# FPGA.net
KiCad netlist of a schematic drawn in Altium Designer
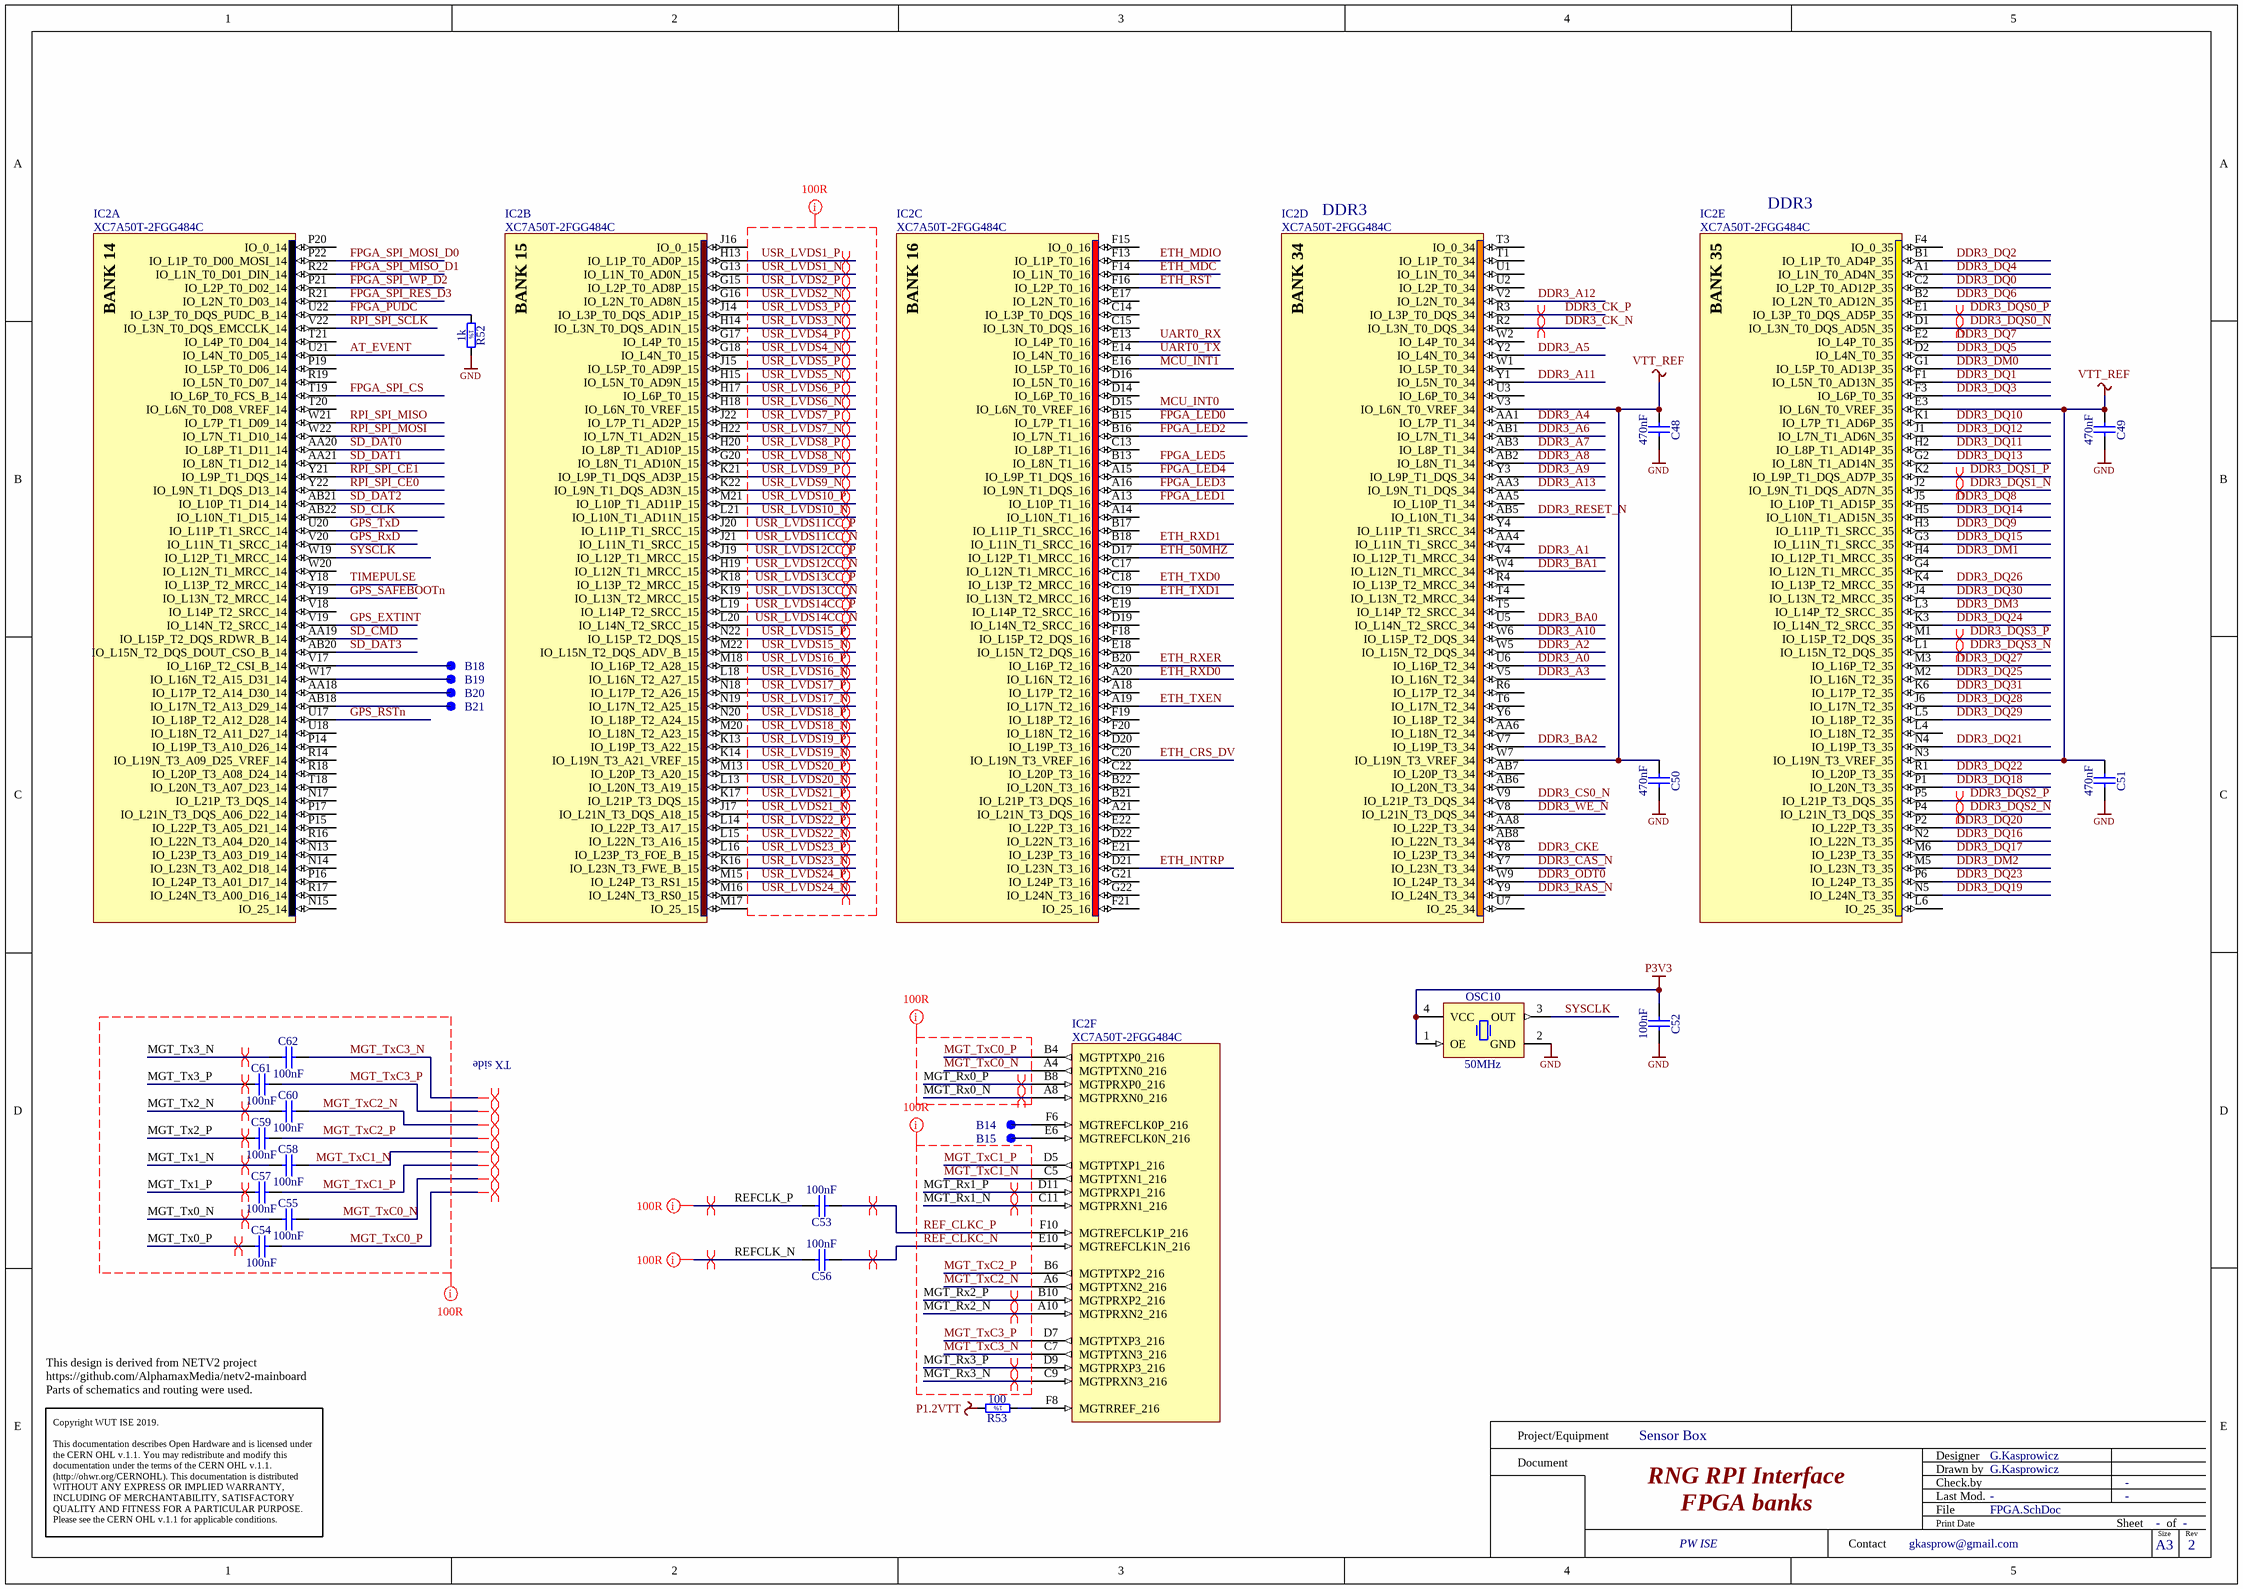
[diagram p0: FPGA.SchDoc]

(export (version "E")
  (design (tool "Eeschema 10.0.6"))
  (components
    (comp (ref "B14")
      (value "SMD Pad")
      (footprint "C100")
      (description "Through Hole Pad")
      (fields (field (name "PART NUMBER") "SMD_PAD_D1MM") (field (name "AUTHOR") "CERN DEM JLC"))
      (libsource (lib "Eletro-mechanical") (part "Single SMD Pad (Round)"))
    )
    (comp (ref "B15")
      (value "SMD Pad")
      (footprint "C100")
      (description "Through Hole Pad")
      (fields (field (name "PART NUMBER") "SMD_PAD_D1MM") (field (name "AUTHOR") "CERN DEM JLC"))
      (libsource (lib "Eletro-mechanical") (part "Single SMD Pad (Round)"))
    )
    (comp (ref "B18")
      (value "SMD Pad")
      (footprint "C100")
      (description "Through Hole Pad")
      (fields (field (name "PART NUMBER") "SMD_PAD_D1MM") (field (name "AUTHOR") "CERN DEM JLC"))
      (libsource (lib "Eletro-mechanical") (part "Single SMD Pad (Round)"))
    )
    (comp (ref "B19")
      (value "SMD Pad")
      (footprint "C100")
      (description "Through Hole Pad")
      (fields (field (name "PART NUMBER") "SMD_PAD_D1MM") (field (name "AUTHOR") "CERN DEM JLC"))
      (libsource (lib "Eletro-mechanical") (part "Single SMD Pad (Round)"))
    )
    (comp (ref "B20")
      (value "SMD Pad")
      (footprint "C100")
      (description "Through Hole Pad")
      (fields (field (name "PART NUMBER") "SMD_PAD_D1MM") (field (name "AUTHOR") "CERN DEM JLC"))
      (libsource (lib "Eletro-mechanical") (part "Single SMD Pad (Round)"))
    )
    (comp (ref "B21")
      (value "SMD Pad")
      (footprint "C100")
      (description "Through Hole Pad")
      (fields (field (name "PART NUMBER") "SMD_PAD_D1MM") (field (name "AUTHOR") "CERN DEM JLC"))
      (libsource (lib "Eletro-mechanical") (part "Single SMD Pad (Round)"))
    )
    (comp (ref "C48")
      (value "470nF")
      (footprint "CAPC0603X33N")
      (description "Non-polarised capacitor")
      (fields
        (field (name "PART NUMBER") "CC0201_470NF_4V_20%_X5R")
        (field (name "VOLTAGE") "4V")
        (field (name "AUTHOR") "CERN DEM JLC")
      )
      (libsource (lib "Capacitors") (part "Capacitor - non polarized"))
    )
    (comp (ref "C49")
      (value "470nF")
      (footprint "CAPC0603X33N")
      (description "Non-polarised capacitor")
      (fields
        (field (name "PART NUMBER") "CC0201_470NF_4V_20%_X5R")
        (field (name "VOLTAGE") "4V")
        (field (name "AUTHOR") "CERN DEM JLC")
      )
      (libsource (lib "Capacitors") (part "Capacitor - non polarized"))
    )
    (comp (ref "C50")
      (value "470nF")
      (footprint "CAPC0603X33N")
      (description "Non-polarised capacitor")
      (fields
        (field (name "PART NUMBER") "CC0201_470NF_4V_20%_X5R")
        (field (name "VOLTAGE") "4V")
        (field (name "AUTHOR") "CERN DEM JLC")
      )
      (libsource (lib "Capacitors") (part "Capacitor - non polarized"))
    )
    (comp (ref "C51")
      (value "470nF")
      (footprint "CAPC0603X33N")
      (description "Non-polarised capacitor")
      (fields
        (field (name "PART NUMBER") "CC0201_470NF_4V_20%_X5R")
        (field (name "VOLTAGE") "4V")
        (field (name "AUTHOR") "CERN DEM JLC")
      )
      (libsource (lib "Capacitors") (part "Capacitor - non polarized"))
    )
    (comp (ref "C52")
      (value "100nF")
      (footprint "CAPC0603X33N")
      (description "Non-polarised capacitor")
      (fields
        (field (name "PART NUMBER") "CC0201_100NF_6.3V_10%_X5R")
        (field (name "VOLTAGE") "6.3V")
        (field (name "AUTHOR") "CERN DEM JLC")
      )
      (libsource (lib "Capacitors") (part "Capacitor - non polarized"))
    )
    (comp (ref "C53")
      (value "100nF")
      (footprint "CAPC0603X33N")
      (description "Non-polarised capacitor")
      (fields
        (field (name "PART NUMBER") "CC0201_100NF_6.3V_10%_X5R")
        (field (name "VOLTAGE") "6.3V")
        (field (name "AUTHOR") "CERN DEM JLC")
      )
      (libsource (lib "Capacitors") (part "Capacitor - non polarized"))
    )
    (comp (ref "C54")
      (value "100nF")
      (footprint "CAPC0603X33N")
      (description "Non-polarised capacitor")
      (fields
        (field (name "PART NUMBER") "CC0201_100NF_6.3V_10%_X5R")
        (field (name "VOLTAGE") "6.3V")
        (field (name "AUTHOR") "CERN DEM JLC")
      )
      (libsource (lib "Capacitors") (part "Capacitor - non polarized"))
    )
    (comp (ref "C55")
      (value "100nF")
      (footprint "CAPC0603X33N")
      (description "Non-polarised capacitor")
      (fields
        (field (name "PART NUMBER") "CC0201_100NF_6.3V_10%_X5R")
        (field (name "VOLTAGE") "6.3V")
        (field (name "AUTHOR") "CERN DEM JLC")
      )
      (libsource (lib "Capacitors") (part "Capacitor - non polarized"))
    )
    (comp (ref "C56")
      (value "100nF")
      (footprint "CAPC0603X33N")
      (description "Non-polarised capacitor")
      (fields
        (field (name "PART NUMBER") "CC0201_100NF_6.3V_10%_X5R")
        (field (name "VOLTAGE") "6.3V")
        (field (name "AUTHOR") "CERN DEM JLC")
      )
      (libsource (lib "Capacitors") (part "Capacitor - non polarized"))
    )
    (comp (ref "C57")
      (value "100nF")
      (footprint "CAPC0603X33N")
      (description "Non-polarised capacitor")
      (fields
        (field (name "PART NUMBER") "CC0201_100NF_6.3V_10%_X5R")
        (field (name "VOLTAGE") "6.3V")
        (field (name "AUTHOR") "CERN DEM JLC")
      )
      (libsource (lib "Capacitors") (part "Capacitor - non polarized"))
    )
    (comp (ref "C58")
      (value "100nF")
      (footprint "CAPC0603X33N")
      (description "Non-polarised capacitor")
      (fields
        (field (name "PART NUMBER") "CC0201_100NF_6.3V_10%_X5R")
        (field (name "VOLTAGE") "6.3V")
        (field (name "AUTHOR") "CERN DEM JLC")
      )
      (libsource (lib "Capacitors") (part "Capacitor - non polarized"))
    )
    (comp (ref "C59")
      (value "100nF")
      (footprint "CAPC0603X33N")
      (description "Non-polarised capacitor")
      (fields
        (field (name "PART NUMBER") "CC0201_100NF_6.3V_10%_X5R")
        (field (name "VOLTAGE") "6.3V")
        (field (name "AUTHOR") "CERN DEM JLC")
      )
      (libsource (lib "Capacitors") (part "Capacitor - non polarized"))
    )
    (comp (ref "C60")
      (value "100nF")
      (footprint "CAPC0603X33N")
      (description "Non-polarised capacitor")
      (fields
        (field (name "PART NUMBER") "CC0201_100NF_6.3V_10%_X5R")
        (field (name "VOLTAGE") "6.3V")
        (field (name "AUTHOR") "CERN DEM JLC")
      )
      (libsource (lib "Capacitors") (part "Capacitor - non polarized"))
    )
    (comp (ref "C61")
      (value "100nF")
      (footprint "CAPC0603X33N")
      (description "Non-polarised capacitor")
      (fields
        (field (name "PART NUMBER") "CC0201_100NF_6.3V_10%_X5R")
        (field (name "VOLTAGE") "6.3V")
        (field (name "AUTHOR") "CERN DEM JLC")
      )
      (libsource (lib "Capacitors") (part "Capacitor - non polarized"))
    )
    (comp (ref "C62")
      (value "100nF")
      (footprint "CAPC0603X33N")
      (description "Non-polarised capacitor")
      (fields
        (field (name "PART NUMBER") "CC0201_100NF_6.3V_10%_X5R")
        (field (name "VOLTAGE") "6.3V")
        (field (name "AUTHOR") "CERN DEM JLC")
      )
      (libsource (lib "Capacitors") (part "Capacitor - non polarized"))
    )
    (comp (ref "IC2")
      (value "XC7A50T-2FGG484C")
      (footprint "BGA484C100P22X22_2300X2300X260")
      (fields (field (name "MANUFACTURER") "XILINX") (field (name "AUTHOR") "CERN DEM JMW"))
      (libsource (lib "ICs And Semiconductors") (part "XC7A50T-2FGG484C"))
    )
    (comp (ref "OSC10")
      (value "50MHz")
      (footprint "OSCSC254P320X500X130-4N")
      (description "Oscillator 4 pins 1=OE 2=GND 3=OUT 4=VCC")
      (fields
        (field (name "PART NUMBER") "OSC_50MHZ_CTS_636L3I050M00000")
        (field (name "MANUFACTURER") "CTS ELECTRONIC COMPONENTS")
        (field (name "AUTHOR") "CERN DEM JMW")
      )
      (libsource (lib "ICs And Semiconductors") (part "Oscillator 1OE 2GND 3OUT 4VCC"))
    )
    (comp (ref "R52")
      (value "1k")
      (footprint "RESC1005X40N")
      (description "Resistor - 1%")
      (fields
        (field (name "PART NUMBER") "R0402_1K_1%_0.0625W_100PPM")
        (field (name "POWER") "0.0625W")
        (field (name "AUTHOR") "CERN DEM JLC")
      )
      (libsource (lib "Resistors") (part "Resistor - 1%"))
    )
    (comp (ref "R53")
      (value "100")
      (footprint "RESC1005X40N")
      (description "Resistor - 1%")
      (fields
        (field (name "PART NUMBER") "R0402_100R_1%_0.1W_100PPM")
        (field (name "POWER") "0.1W")
        (field (name "AUTHOR") "CERN DEM JLC")
      )
      (libsource (lib "Resistors") (part "Resistor - 1%"))
    )
  )
  (nets
    (net (code "1") (name "/AT_EVENT") (class "Default")
      (node (ref "IC2") (pin "U21") (pinfunction "IO_L4N_T0_D05_14_U21") (pintype "bidirectional"))
    )
    (net (code "2") (name "/DDR3_A0") (class "Default")
      (node (ref "IC2") (pin "U6") (pinfunction "IO_L16P_T2_34_U6") (pintype "bidirectional"))
    )
    (net (code "3") (name "/DDR3_A1") (class "Default")
      (node (ref "IC2") (pin "V4") (pinfunction "IO_L12P_T1_MRCC_34_V4") (pintype "bidirectional"))
    )
    (net (code "4") (name "/DDR3_A2") (class "Default")
      (node (ref "IC2") (pin "W5") (pinfunction "IO_L15N_T2_DQS_34_W5") (pintype "bidirectional"))
    )
    (net (code "5") (name "/DDR3_A3") (class "Default")
      (node (ref "IC2") (pin "V5") (pinfunction "IO_L16N_T2_34_V5") (pintype "bidirectional"))
    )
    (net (code "6") (name "/DDR3_A4") (class "Default")
      (node (ref "IC2") (pin "AA1") (pinfunction "IO_L7P_T1_34_AA1") (pintype "bidirectional"))
    )
    (net (code "7") (name "/DDR3_A5") (class "Default")
      (node (ref "IC2") (pin "Y2") (pinfunction "IO_L4N_T0_34_Y2") (pintype "bidirectional"))
    )
    (net (code "8") (name "/DDR3_A6") (class "Default")
      (node (ref "IC2") (pin "AB1") (pinfunction "IO_L7N_T1_34_AB1") (pintype "bidirectional"))
    )
    (net (code "9") (name "/DDR3_A7") (class "Default")
      (node (ref "IC2") (pin "AB3") (pinfunction "IO_L8P_T1_34_AB3") (pintype "bidirectional"))
    )
    (net (code "10") (name "/DDR3_A8") (class "Default")
      (node (ref "IC2") (pin "AB2") (pinfunction "IO_L8N_T1_34_AB2") (pintype "bidirectional"))
    )
    (net (code "11") (name "/DDR3_A9") (class "Default")
      (node (ref "IC2") (pin "Y3") (pinfunction "IO_L9P_T1_DQS_34_Y3") (pintype "bidirectional"))
    )
    (net (code "12") (name "/DDR3_A10") (class "Default")
      (node (ref "IC2") (pin "W6") (pinfunction "IO_L15P_T2_DQS_34_W6") (pintype "bidirectional"))
    )
    (net (code "13") (name "/DDR3_A11") (class "Default")
      (node (ref "IC2") (pin "Y1") (pinfunction "IO_L5N_T0_34_Y1") (pintype "bidirectional"))
    )
    (net (code "14") (name "/DDR3_A12") (class "Default")
      (node (ref "IC2") (pin "V2") (pinfunction "IO_L2N_T0_34_V2") (pintype "bidirectional"))
    )
    (net (code "15") (name "/DDR3_A13") (class "Default")
      (node (ref "IC2") (pin "AA3") (pinfunction "IO_L9N_T1_DQS_34_AA3") (pintype "bidirectional"))
    )
    (net (code "16") (name "/DDR3_BA0") (class "Default")
      (node (ref "IC2") (pin "U5") (pinfunction "IO_L14N_T2_SRCC_34_U5") (pintype "bidirectional"))
    )
    (net (code "17") (name "/DDR3_BA1") (class "Default")
      (node (ref "IC2") (pin "W4") (pinfunction "IO_L12N_T1_MRCC_34_W4") (pintype "bidirectional"))
    )
    (net (code "18") (name "/DDR3_BA2") (class "Default")
      (node (ref "IC2") (pin "V7") (pinfunction "IO_L19P_T3_34_V7") (pintype "bidirectional"))
    )
    (net (code "19") (name "/DDR3_CAS_N") (class "Default")
      (node (ref "IC2") (pin "Y7") (pinfunction "IO_L23N_T3_34_Y7") (pintype "bidirectional"))
    )
    (net (code "20") (name "/DDR3_CKE") (class "Default")
      (node (ref "IC2") (pin "Y8") (pinfunction "IO_L23P_T3_34_Y8") (pintype "bidirectional"))
    )
    (net (code "21") (name "/DDR3_CK_N") (class "Default")
      (node (ref "IC2") (pin "R2") (pinfunction "IO_L3N_T0_DQS_34_R2") (pintype "bidirectional"))
    )
    (net (code "22") (name "/DDR3_CK_P") (class "Default")
      (node (ref "IC2") (pin "R3") (pinfunction "IO_L3P_T0_DQS_34_R3") (pintype "bidirectional"))
    )
    (net (code "23") (name "/DDR3_CS0_N") (class "Default")
      (node (ref "IC2") (pin "V9") (pinfunction "IO_L21P_T3_DQS_34_V9") (pintype "bidirectional"))
    )
    (net (code "24") (name "/DDR3_DM0") (class "Default")
      (node (ref "IC2") (pin "G1") (pinfunction "IO_L5P_T0_AD13P_35_G1") (pintype "bidirectional"))
    )
    (net (code "25") (name "/DDR3_DM1") (class "Default")
      (node (ref "IC2") (pin "H4") (pinfunction "IO_L12P_T1_MRCC_35_H4") (pintype "bidirectional"))
    )
    (net (code "26") (name "/DDR3_DM2") (class "Default")
      (node (ref "IC2") (pin "M5") (pinfunction "IO_L23N_T3_35_M5") (pintype "bidirectional"))
    )
    (net (code "27") (name "/DDR3_DM3") (class "Default")
      (node (ref "IC2") (pin "L3") (pinfunction "IO_L14P_T2_SRCC_35_L3") (pintype "bidirectional"))
    )
    (net (code "28") (name "/DDR3_DQ0") (class "Default")
      (node (ref "IC2") (pin "C2") (pinfunction "IO_L2P_T0_AD12P_35_C2") (pintype "bidirectional"))
    )
    (net (code "29") (name "/DDR3_DQ1") (class "Default")
      (node (ref "IC2") (pin "F1") (pinfunction "IO_L5N_T0_AD13N_35_F1") (pintype "bidirectional"))
    )
    (net (code "30") (name "/DDR3_DQ2") (class "Default")
      (node (ref "IC2") (pin "B1") (pinfunction "IO_L1P_T0_AD4P_35_B1") (pintype "bidirectional"))
    )
    (net (code "31") (name "/DDR3_DQ3") (class "Default")
      (node (ref "IC2") (pin "F3") (pinfunction "IO_L6P_T0_35_F3") (pintype "bidirectional"))
    )
    (net (code "32") (name "/DDR3_DQ4") (class "Default")
      (node (ref "IC2") (pin "A1") (pinfunction "IO_L1N_T0_AD4N_35_A1") (pintype "bidirectional"))
    )
    (net (code "33") (name "/DDR3_DQ5") (class "Default")
      (node (ref "IC2") (pin "D2") (pinfunction "IO_L4N_T0_35_D2") (pintype "bidirectional"))
    )
    (net (code "34") (name "/DDR3_DQ6") (class "Default")
      (node (ref "IC2") (pin "B2") (pinfunction "IO_L2N_T0_AD12N_35_B2") (pintype "bidirectional"))
    )
    (net (code "35") (name "/DDR3_DQ7") (class "Default")
      (node (ref "IC2") (pin "E2") (pinfunction "IO_L4P_T0_35_E2") (pintype "bidirectional"))
    )
    (net (code "36") (name "/DDR3_DQ8") (class "Default")
      (node (ref "IC2") (pin "J5") (pinfunction "IO_L10P_T1_AD15P_35_J5") (pintype "bidirectional"))
    )
    (net (code "37") (name "/DDR3_DQ9") (class "Default")
      (node (ref "IC2") (pin "H3") (pinfunction "IO_L11P_T1_SRCC_35_H3") (pintype "bidirectional"))
    )
    (net (code "38") (name "/DDR3_DQ10") (class "Default")
      (node (ref "IC2") (pin "K1") (pinfunction "IO_L7P_T1_AD6P_35_K1") (pintype "bidirectional"))
    )
    (net (code "39") (name "/DDR3_DQ11") (class "Default")
      (node (ref "IC2") (pin "H2") (pinfunction "IO_L8P_T1_AD14P_35_H2") (pintype "bidirectional"))
    )
    (net (code "40") (name "/DDR3_DQ12") (class "Default")
      (node (ref "IC2") (pin "J1") (pinfunction "IO_L7N_T1_AD6N_35_J1") (pintype "bidirectional"))
    )
    (net (code "41") (name "/DDR3_DQ13") (class "Default")
      (node (ref "IC2") (pin "G2") (pinfunction "IO_L8N_T1_AD14N_35_G2") (pintype "bidirectional"))
    )
    (net (code "42") (name "/DDR3_DQ14") (class "Default")
      (node (ref "IC2") (pin "H5") (pinfunction "IO_L10N_T1_AD15N_35_H5") (pintype "bidirectional"))
    )
    (net (code "43") (name "/DDR3_DQ15") (class "Default")
      (node (ref "IC2") (pin "G3") (pinfunction "IO_L11N_T1_SRCC_35_G3") (pintype "bidirectional"))
    )
    (net (code "44") (name "/DDR3_DQ16") (class "Default")
      (node (ref "IC2") (pin "N2") (pinfunction "IO_L22N_T3_35_N2") (pintype "bidirectional"))
    )
    (net (code "45") (name "/DDR3_DQ17") (class "Default")
      (node (ref "IC2") (pin "M6") (pinfunction "IO_L23P_T3_35_M6") (pintype "bidirectional"))
    )
    (net (code "46") (name "/DDR3_DQ18") (class "Default")
      (node (ref "IC2") (pin "P1") (pinfunction "IO_L20N_T3_35_P1") (pintype "bidirectional"))
    )
    (net (code "47") (name "/DDR3_DQ19") (class "Default")
      (node (ref "IC2") (pin "N5") (pinfunction "IO_L24N_T3_35_N5") (pintype "bidirectional"))
    )
    (net (code "48") (name "/DDR3_DQ20") (class "Default")
      (node (ref "IC2") (pin "P2") (pinfunction "IO_L22P_T3_35_P2") (pintype "bidirectional"))
    )
    (net (code "49") (name "/DDR3_DQ21") (class "Default")
      (node (ref "IC2") (pin "N4") (pinfunction "IO_L19P_T3_35_N4") (pintype "bidirectional"))
    )
    (net (code "50") (name "/DDR3_DQ22") (class "Default")
      (node (ref "IC2") (pin "R1") (pinfunction "IO_L20P_T3_35_R1") (pintype "bidirectional"))
    )
    (net (code "51") (name "/DDR3_DQ23") (class "Default")
      (node (ref "IC2") (pin "P6") (pinfunction "IO_L24P_T3_35_P6") (pintype "bidirectional"))
    )
    (net (code "52") (name "/DDR3_DQ24") (class "Default")
      (node (ref "IC2") (pin "K3") (pinfunction "IO_L14N_T2_SRCC_35_K3") (pintype "bidirectional"))
    )
    (net (code "53") (name "/DDR3_DQ25") (class "Default")
      (node (ref "IC2") (pin "M2") (pinfunction "IO_L16N_T2_35_M2") (pintype "bidirectional"))
    )
    (net (code "54") (name "/DDR3_DQ26") (class "Default")
      (node (ref "IC2") (pin "K4") (pinfunction "IO_L13P_T2_MRCC_35_K4") (pintype "bidirectional"))
    )
    (net (code "55") (name "/DDR3_DQ27") (class "Default")
      (node (ref "IC2") (pin "M3") (pinfunction "IO_L16P_T2_35_M3") (pintype "bidirectional"))
    )
    (net (code "56") (name "/DDR3_DQ28") (class "Default")
      (node (ref "IC2") (pin "J6") (pinfunction "IO_L17N_T2_35_J6") (pintype "bidirectional"))
    )
    (net (code "57") (name "/DDR3_DQ29") (class "Default")
      (node (ref "IC2") (pin "L5") (pinfunction "IO_L18P_T2_35_L5") (pintype "bidirectional"))
    )
    (net (code "58") (name "/DDR3_DQ30") (class "Default")
      (node (ref "IC2") (pin "J4") (pinfunction "IO_L13N_T2_MRCC_35_J4") (pintype "bidirectional"))
    )
    (net (code "59") (name "/DDR3_DQ31") (class "Default")
      (node (ref "IC2") (pin "K6") (pinfunction "IO_L17P_T2_35_K6") (pintype "bidirectional"))
    )
    (net (code "60") (name "/DDR3_DQS0_N") (class "Default")
      (node (ref "IC2") (pin "D1") (pinfunction "IO_L3N_T0_DQS_AD5N_35_D1") (pintype "bidirectional"))
    )
    (net (code "61") (name "/DDR3_DQS0_P") (class "Default")
      (node (ref "IC2") (pin "E1") (pinfunction "IO_L3P_T0_DQS_AD5P_35_E1") (pintype "bidirectional"))
    )
    (net (code "62") (name "/DDR3_DQS1_N") (class "Default")
      (node (ref "IC2") (pin "J2") (pinfunction "IO_L9N_T1_DQS_AD7N_35_J2") (pintype "bidirectional"))
    )
    (net (code "63") (name "/DDR3_DQS1_P") (class "Default")
      (node (ref "IC2") (pin "K2") (pinfunction "IO_L9P_T1_DQS_AD7P_35_K2") (pintype "bidirectional"))
    )
    (net (code "64") (name "/DDR3_DQS2_N") (class "Default")
      (node (ref "IC2") (pin "P4") (pinfunction "IO_L21N_T3_DQS_35_P4") (pintype "bidirectional"))
    )
    (net (code "65") (name "/DDR3_DQS2_P") (class "Default")
      (node (ref "IC2") (pin "P5") (pinfunction "IO_L21P_T3_DQS_35_P5") (pintype "bidirectional"))
    )
    (net (code "66") (name "/DDR3_DQS3_N") (class "Default")
      (node (ref "IC2") (pin "L1") (pinfunction "IO_L15N_T2_DQS_35_L1") (pintype "bidirectional"))
    )
    (net (code "67") (name "/DDR3_DQS3_P") (class "Default")
      (node (ref "IC2") (pin "M1") (pinfunction "IO_L15P_T2_DQS_35_M1") (pintype "bidirectional"))
    )
    (net (code "68") (name "/DDR3_ODT0") (class "Default")
      (node (ref "IC2") (pin "W9") (pinfunction "IO_L24P_T3_34_W9") (pintype "bidirectional"))
    )
    (net (code "69") (name "/DDR3_RAS_N") (class "Default")
      (node (ref "IC2") (pin "Y9") (pinfunction "IO_L24N_T3_34_Y9") (pintype "bidirectional"))
    )
    (net (code "70") (name "/DDR3_RESET_N") (class "Default")
      (node (ref "IC2") (pin "AB5") (pinfunction "IO_L10N_T1_34_AB5") (pintype "bidirectional"))
    )
    (net (code "71") (name "/DDR3_WE_N") (class "Default")
      (node (ref "IC2") (pin "V8") (pinfunction "IO_L21N_T3_DQS_34_V8") (pintype "bidirectional"))
    )
    (net (code "72") (name "/ETH_50MHZ") (class "Default")
      (node (ref "IC2") (pin "D17") (pinfunction "IO_L12P_T1_MRCC_16_D17") (pintype "bidirectional"))
    )
    (net (code "73") (name "/ETH_CRS_DV") (class "Default")
      (node (ref "IC2") (pin "C20") (pinfunction "IO_L19N_T3_VREF_16_C20") (pintype "bidirectional"))
    )
    (net (code "74") (name "/ETH_INTRP") (class "Default")
      (node (ref "IC2") (pin "D21") (pinfunction "IO_L23N_T3_16_D21") (pintype "bidirectional"))
    )
    (net (code "75") (name "/ETH_MDC") (class "Default")
      (node (ref "IC2") (pin "F14") (pinfunction "IO_L1N_T0_16_F14") (pintype "bidirectional"))
    )
    (net (code "76") (name "/ETH_MDIO") (class "Default")
      (node (ref "IC2") (pin "F13") (pinfunction "IO_L1P_T0_16_F13") (pintype "bidirectional"))
    )
    (net (code "77") (name "/ETH_RST") (class "Default")
      (node (ref "IC2") (pin "F16") (pinfunction "IO_L2P_T0_16_F16") (pintype "bidirectional"))
    )
    (net (code "78") (name "/ETH_RXD0") (class "Default")
      (node (ref "IC2") (pin "A20") (pinfunction "IO_L16N_T2_16_A20") (pintype "bidirectional"))
    )
    (net (code "79") (name "/ETH_RXD1") (class "Default")
      (node (ref "IC2") (pin "B18") (pinfunction "IO_L11N_T1_SRCC_16_B18") (pintype "bidirectional"))
    )
    (net (code "80") (name "/ETH_RXER") (class "Default")
      (node (ref "IC2") (pin "B20") (pinfunction "IO_L16P_T2_16_B20") (pintype "bidirectional"))
    )
    (net (code "81") (name "/ETH_TXD0") (class "Default")
      (node (ref "IC2") (pin "C18") (pinfunction "IO_L13P_T2_MRCC_16_C18") (pintype "bidirectional"))
    )
    (net (code "82") (name "/ETH_TXD1") (class "Default")
      (node (ref "IC2") (pin "C19") (pinfunction "IO_L13N_T2_MRCC_16_C19") (pintype "bidirectional"))
    )
    (net (code "83") (name "/ETH_TXEN") (class "Default")
      (node (ref "IC2") (pin "A19") (pinfunction "IO_L17N_T2_16_A19") (pintype "bidirectional"))
    )
    (net (code "84") (name "/FPGA_LED0") (class "Default")
      (node (ref "IC2") (pin "B15") (pinfunction "IO_L7P_T1_16_B15") (pintype "bidirectional"))
    )
    (net (code "85") (name "/FPGA_LED1") (class "Default")
      (node (ref "IC2") (pin "A13") (pinfunction "IO_L10P_T1_16_A13") (pintype "bidirectional"))
    )
    (net (code "86") (name "/FPGA_LED2") (class "Default")
      (node (ref "IC2") (pin "B16") (pinfunction "IO_L7N_T1_16_B16") (pintype "bidirectional"))
    )
    (net (code "87") (name "/FPGA_LED3") (class "Default")
      (node (ref "IC2") (pin "A16") (pinfunction "IO_L9N_T1_DQS_16_A16") (pintype "bidirectional"))
    )
    (net (code "88") (name "/FPGA_LED4") (class "Default")
      (node (ref "IC2") (pin "A15") (pinfunction "IO_L9P_T1_DQS_16_A15") (pintype "bidirectional"))
    )
    (net (code "89") (name "/FPGA_LED5") (class "Default")
      (node (ref "IC2") (pin "B13") (pinfunction "IO_L8N_T1_16_B13") (pintype "bidirectional"))
    )
    (net (code "90") (name "/FPGA_PUDC") (class "Default")
      (node (ref "IC2") (pin "U22") (pinfunction "IO_L3P_T0_DQS_PUDC_B_14_U22") (pintype "bidirectional"))
      (node (ref "R52") (pin "1") (pinfunction "1_1") (pintype "passive"))
    )
    (net (code "91") (name "/FPGA_SPI_CS") (class "Default")
      (node (ref "IC2") (pin "T19") (pinfunction "IO_L6P_T0_FCS_B_14_T19") (pintype "bidirectional"))
    )
    (net (code "92") (name "/FPGA_SPI_MISO_D1") (class "Default")
      (node (ref "IC2") (pin "R22") (pinfunction "IO_L1N_T0_D01_DIN_14_R22") (pintype "bidirectional"))
    )
    (net (code "93") (name "/FPGA_SPI_MOSI_D0") (class "Default")
      (node (ref "IC2") (pin "P22") (pinfunction "IO_L1P_T0_D00_MOSI_14_P22") (pintype "bidirectional"))
    )
    (net (code "94") (name "/FPGA_SPI_RES_D3") (class "Default")
      (node (ref "IC2") (pin "R21") (pinfunction "IO_L2N_T0_D03_14_R21") (pintype "bidirectional"))
    )
    (net (code "95") (name "/FPGA_SPI_WP_D2") (class "Default")
      (node (ref "IC2") (pin "P21") (pinfunction "IO_L2P_T0_D02_14_P21") (pintype "bidirectional"))
    )
    (net (code "96") (name "/GPS_EXTINT") (class "Default")
      (node (ref "IC2") (pin "V19") (pinfunction "IO_L14N_T2_SRCC_14_V19") (pintype "bidirectional"))
    )
    (net (code "97") (name "/GPS_RSTn") (class "Default")
      (node (ref "IC2") (pin "U17") (pinfunction "IO_L18P_T2_A12_D28_14_U17") (pintype "bidirectional"))
    )
    (net (code "98") (name "/GPS_RxD") (class "Default")
      (node (ref "IC2") (pin "V20") (pinfunction "IO_L11N_T1_SRCC_14_V20") (pintype "bidirectional"))
    )
    (net (code "99") (name "/GPS_SAFEBOOTn") (class "Default")
      (node (ref "IC2") (pin "Y19") (pinfunction "IO_L13N_T2_MRCC_14_Y19") (pintype "bidirectional"))
    )
    (net (code "100") (name "/GPS_TxD") (class "Default")
      (node (ref "IC2") (pin "U20") (pinfunction "IO_L11P_T1_SRCC_14_U20") (pintype "bidirectional"))
    )
    (net (code "101") (name "/MCU_INT0") (class "Default")
      (node (ref "IC2") (pin "D15") (pinfunction "IO_L6N_T0_VREF_16_D15") (pintype "bidirectional"))
    )
    (net (code "102") (name "/MCU_INT1") (class "Default")
      (node (ref "IC2") (pin "E16") (pinfunction "IO_L5P_T0_16_E16") (pintype "bidirectional"))
    )
    (net (code "103") (name "/MGT_Rx0_N") (class "Default")
      (node (ref "IC2") (pin "A8") (pinfunction "MGTPRXN0_216_A8") (pintype "input"))
    )
    (net (code "104") (name "/MGT_Rx0_P") (class "Default")
      (node (ref "IC2") (pin "B8") (pinfunction "MGTPRXP0_216_B8") (pintype "input"))
    )
    (net (code "105") (name "/MGT_Rx1_N") (class "Default")
      (node (ref "IC2") (pin "C11") (pinfunction "MGTPRXN1_216_C11") (pintype "input"))
    )
    (net (code "106") (name "/MGT_Rx1_P") (class "Default")
      (node (ref "IC2") (pin "D11") (pinfunction "MGTPRXP1_216_D11") (pintype "input"))
    )
    (net (code "107") (name "/MGT_Rx2_N") (class "Default")
      (node (ref "IC2") (pin "A10") (pinfunction "MGTPRXN2_216_A10") (pintype "input"))
    )
    (net (code "108") (name "/MGT_Rx2_P") (class "Default")
      (node (ref "IC2") (pin "B10") (pinfunction "MGTPRXP2_216_B10") (pintype "input"))
    )
    (net (code "109") (name "/MGT_Rx3_N") (class "Default")
      (node (ref "IC2") (pin "C9") (pinfunction "MGTPRXN3_216_C9") (pintype "input"))
    )
    (net (code "110") (name "/MGT_Rx3_P") (class "Default")
      (node (ref "IC2") (pin "D9") (pinfunction "MGTPRXP3_216_D9") (pintype "input"))
    )
    (net (code "111") (name "/MGT_Tx0_N") (class "Default")
      (node (ref "C55") (pin "1") (pinfunction "1_1") (pintype "passive"))
    )
    (net (code "112") (name "/MGT_Tx0_P") (class "Default")
      (node (ref "C54") (pin "1") (pinfunction "1_1") (pintype "passive"))
    )
    (net (code "113") (name "/MGT_Tx1_N") (class "Default")
      (node (ref "C58") (pin "1") (pinfunction "1_1") (pintype "passive"))
    )
    (net (code "114") (name "/MGT_Tx1_P") (class "Default")
      (node (ref "C57") (pin "1") (pinfunction "1_1") (pintype "passive"))
    )
    (net (code "115") (name "/MGT_Tx2_N") (class "Default")
      (node (ref "C60") (pin "1") (pinfunction "1_1") (pintype "passive"))
    )
    (net (code "116") (name "/MGT_Tx2_P") (class "Default")
      (node (ref "C59") (pin "1") (pinfunction "1_1") (pintype "passive"))
    )
    (net (code "117") (name "/MGT_Tx3_N") (class "Default")
      (node (ref "C62") (pin "1") (pinfunction "1_1") (pintype "passive"))
    )
    (net (code "118") (name "/MGT_Tx3_P") (class "Default")
      (node (ref "C61") (pin "1") (pinfunction "1_1") (pintype "passive"))
    )
    (net (code "119") (name "/MGT_TxC0_N") (class "Default")
      (node (ref "C55") (pin "2") (pinfunction "2_2") (pintype "passive"))
      (node (ref "IC2") (pin "A4") (pinfunction "MGTPTXN0_216_A4") (pintype "output"))
    )
    (net (code "120") (name "/MGT_TxC0_P") (class "Default")
      (node (ref "C54") (pin "2") (pinfunction "2_2") (pintype "passive"))
      (node (ref "IC2") (pin "B4") (pinfunction "MGTPTXP0_216_B4") (pintype "output"))
    )
    (net (code "121") (name "/MGT_TxC1_N") (class "Default")
      (node (ref "C58") (pin "2") (pinfunction "2_2") (pintype "passive"))
      (node (ref "IC2") (pin "C5") (pinfunction "MGTPTXN1_216_C5") (pintype "output"))
    )
    (net (code "122") (name "/MGT_TxC1_P") (class "Default")
      (node (ref "C57") (pin "2") (pinfunction "2_2") (pintype "passive"))
      (node (ref "IC2") (pin "D5") (pinfunction "MGTPTXP1_216_D5") (pintype "output"))
    )
    (net (code "123") (name "/MGT_TxC2_N") (class "Default")
      (node (ref "C60") (pin "2") (pinfunction "2_2") (pintype "passive"))
      (node (ref "IC2") (pin "A6") (pinfunction "MGTPTXN2_216_A6") (pintype "output"))
    )
    (net (code "124") (name "/MGT_TxC2_P") (class "Default")
      (node (ref "C59") (pin "2") (pinfunction "2_2") (pintype "passive"))
      (node (ref "IC2") (pin "B6") (pinfunction "MGTPTXP2_216_B6") (pintype "output"))
    )
    (net (code "125") (name "/MGT_TxC3_N") (class "Default")
      (node (ref "C62") (pin "2") (pinfunction "2_2") (pintype "passive"))
      (node (ref "IC2") (pin "C7") (pinfunction "MGTPTXN3_216_C7") (pintype "output"))
    )
    (net (code "126") (name "/MGT_TxC3_P") (class "Default")
      (node (ref "C61") (pin "2") (pinfunction "2_2") (pintype "passive"))
      (node (ref "IC2") (pin "D7") (pinfunction "MGTPTXP3_216_D7") (pintype "output"))
    )
    (net (code "127") (name "/REFCLK_N") (class "Default")
      (node (ref "C56") (pin "2") (pinfunction "2_2") (pintype "passive"))
    )
    (net (code "128") (name "/REFCLK_P") (class "Default")
      (node (ref "C53") (pin "2") (pinfunction "2_2") (pintype "passive"))
    )
    (net (code "129") (name "/REF_CLKC_N") (class "Default")
      (node (ref "C56") (pin "1") (pinfunction "1_1") (pintype "passive"))
      (node (ref "IC2") (pin "E10") (pinfunction "MGTREFCLK1N_216_E10") (pintype "input"))
    )
    (net (code "130") (name "/REF_CLKC_P") (class "Default")
      (node (ref "C53") (pin "1") (pinfunction "1_1") (pintype "passive"))
      (node (ref "IC2") (pin "F10") (pinfunction "MGTREFCLK1P_216_F10") (pintype "input"))
    )
    (net (code "131") (name "/RPI_SPI_CE0") (class "Default")
      (node (ref "IC2") (pin "Y22") (pinfunction "IO_L9N_T1_DQS_D13_14_Y22") (pintype "bidirectional"))
    )
    (net (code "132") (name "/RPI_SPI_CE1") (class "Default")
      (node (ref "IC2") (pin "Y21") (pinfunction "IO_L9P_T1_DQS_14_Y21") (pintype "bidirectional"))
    )
    (net (code "133") (name "/RPI_SPI_MISO") (class "Default")
      (node (ref "IC2") (pin "W21") (pinfunction "IO_L7P_T1_D09_14_W21") (pintype "bidirectional"))
    )
    (net (code "134") (name "/RPI_SPI_MOSI") (class "Default")
      (node (ref "IC2") (pin "W22") (pinfunction "IO_L7N_T1_D10_14_W22") (pintype "bidirectional"))
    )
    (net (code "135") (name "/RPI_SPI_SCLK") (class "Default")
      (node (ref "IC2") (pin "V22") (pinfunction "IO_L3N_T0_DQS_EMCCLK_14_V22") (pintype "bidirectional"))
    )
    (net (code "136") (name "/SD_CLK") (class "Default")
      (node (ref "IC2") (pin "AB22") (pinfunction "IO_L10N_T1_D15_14_AB22") (pintype "bidirectional"))
    )
    (net (code "137") (name "/SD_CMD") (class "Default")
      (node (ref "IC2") (pin "AA19") (pinfunction "IO_L15P_T2_DQS_RDWR_B_14_AA19") (pintype "bidirectional"))
    )
    (net (code "138") (name "/SD_DAT0") (class "Default")
      (node (ref "IC2") (pin "AA20") (pinfunction "IO_L8P_T1_D11_14_AA20") (pintype "bidirectional"))
    )
    (net (code "139") (name "/SD_DAT1") (class "Default")
      (node (ref "IC2") (pin "AA21") (pinfunction "IO_L8N_T1_D12_14_AA21") (pintype "bidirectional"))
    )
    (net (code "140") (name "/SD_DAT2") (class "Default")
      (node (ref "IC2") (pin "AB21") (pinfunction "IO_L10P_T1_D14_14_AB21") (pintype "bidirectional"))
    )
    (net (code "141") (name "/SD_DAT3") (class "Default")
      (node (ref "IC2") (pin "AB20") (pinfunction "IO_L15N_T2_DQS_DOUT_CSO_B_14_AB20") (pintype "bidirectional"))
    )
    (net (code "142") (name "/SYSCLK") (class "Default")
      (node (ref "IC2") (pin "W19") (pinfunction "IO_L12P_T1_MRCC_14_W19") (pintype "bidirectional"))
      (node (ref "OSC10") (pin "3") (pinfunction "OUT_3") (pintype "output"))
    )
    (net (code "143") (name "/TIMEPULSE") (class "Default")
      (node (ref "IC2") (pin "Y18") (pinfunction "IO_L13P_T2_MRCC_14_Y18") (pintype "bidirectional"))
    )
    (net (code "144") (name "/UART0_RX") (class "Default")
      (node (ref "IC2") (pin "E13") (pinfunction "IO_L4P_T0_16_E13") (pintype "bidirectional"))
    )
    (net (code "145") (name "/UART0_TX") (class "Default")
      (node (ref "IC2") (pin "E14") (pinfunction "IO_L4N_T0_16_E14") (pintype "bidirectional"))
    )
    (net (code "146") (name "/USR_LVDS1_N") (class "Default")
      (node (ref "IC2") (pin "G13") (pinfunction "IO_L1N_T0_AD0N_15_G13") (pintype "bidirectional"))
    )
    (net (code "147") (name "/USR_LVDS1_P") (class "Default")
      (node (ref "IC2") (pin "H13") (pinfunction "IO_L1P_T0_AD0P_15_H13") (pintype "bidirectional"))
    )
    (net (code "148") (name "/USR_LVDS2_N") (class "Default")
      (node (ref "IC2") (pin "G16") (pinfunction "IO_L2N_T0_AD8N_15_G16") (pintype "bidirectional"))
    )
    (net (code "149") (name "/USR_LVDS2_P") (class "Default")
      (node (ref "IC2") (pin "G15") (pinfunction "IO_L2P_T0_AD8P_15_G15") (pintype "bidirectional"))
    )
    (net (code "150") (name "/USR_LVDS3_N") (class "Default")
      (node (ref "IC2") (pin "H14") (pinfunction "IO_L3N_T0_DQS_AD1N_15_H14") (pintype "bidirectional"))
    )
    (net (code "151") (name "/USR_LVDS3_P") (class "Default")
      (node (ref "IC2") (pin "J14") (pinfunction "IO_L3P_T0_DQS_AD1P_15_J14") (pintype "bidirectional"))
    )
    (net (code "152") (name "/USR_LVDS4_N") (class "Default")
      (node (ref "IC2") (pin "G18") (pinfunction "IO_L4N_T0_15_G18") (pintype "bidirectional"))
    )
    (net (code "153") (name "/USR_LVDS4_P") (class "Default")
      (node (ref "IC2") (pin "G17") (pinfunction "IO_L4P_T0_15_G17") (pintype "bidirectional"))
    )
    (net (code "154") (name "/USR_LVDS5_N") (class "Default")
      (node (ref "IC2") (pin "H15") (pinfunction "IO_L5N_T0_AD9N_15_H15") (pintype "bidirectional"))
    )
    (net (code "155") (name "/USR_LVDS5_P") (class "Default")
      (node (ref "IC2") (pin "J15") (pinfunction "IO_L5P_T0_AD9P_15_J15") (pintype "bidirectional"))
    )
    (net (code "156") (name "/USR_LVDS6_N") (class "Default")
      (node (ref "IC2") (pin "H18") (pinfunction "IO_L6N_T0_VREF_15_H18") (pintype "bidirectional"))
    )
    (net (code "157") (name "/USR_LVDS6_P") (class "Default")
      (node (ref "IC2") (pin "H17") (pinfunction "IO_L6P_T0_15_H17") (pintype "bidirectional"))
    )
    (net (code "158") (name "/USR_LVDS7_N") (class "Default")
      (node (ref "IC2") (pin "H22") (pinfunction "IO_L7N_T1_AD2N_15_H22") (pintype "bidirectional"))
    )
    (net (code "159") (name "/USR_LVDS7_P") (class "Default")
      (node (ref "IC2") (pin "J22") (pinfunction "IO_L7P_T1_AD2P_15_J22") (pintype "bidirectional"))
    )
    (net (code "160") (name "/USR_LVDS8_N") (class "Default")
      (node (ref "IC2") (pin "G20") (pinfunction "IO_L8N_T1_AD10N_15_G20") (pintype "bidirectional"))
    )
    (net (code "161") (name "/USR_LVDS8_P") (class "Default")
      (node (ref "IC2") (pin "H20") (pinfunction "IO_L8P_T1_AD10P_15_H20") (pintype "bidirectional"))
    )
    (net (code "162") (name "/USR_LVDS9_N") (class "Default")
      (node (ref "IC2") (pin "K22") (pinfunction "IO_L9N_T1_DQS_AD3N_15_K22") (pintype "bidirectional"))
    )
    (net (code "163") (name "/USR_LVDS9_P") (class "Default")
      (node (ref "IC2") (pin "K21") (pinfunction "IO_L9P_T1_DQS_AD3P_15_K21") (pintype "bidirectional"))
    )
    (net (code "164") (name "/USR_LVDS10_N") (class "Default")
      (node (ref "IC2") (pin "L21") (pinfunction "IO_L10N_T1_AD11N_15_L21") (pintype "bidirectional"))
    )
    (net (code "165") (name "/USR_LVDS10_P") (class "Default")
      (node (ref "IC2") (pin "M21") (pinfunction "IO_L10P_T1_AD11P_15_M21") (pintype "bidirectional"))
    )
    (net (code "166") (name "/USR_LVDS11CC_N") (class "Default")
      (node (ref "IC2") (pin "J21") (pinfunction "IO_L11N_T1_SRCC_15_J21") (pintype "bidirectional"))
    )
    (net (code "167") (name "/USR_LVDS11CC_P") (class "Default")
      (node (ref "IC2") (pin "J20") (pinfunction "IO_L11P_T1_SRCC_15_J20") (pintype "bidirectional"))
    )
    (net (code "168") (name "/USR_LVDS12CC_N") (class "Default")
      (node (ref "IC2") (pin "H19") (pinfunction "IO_L12N_T1_MRCC_15_H19") (pintype "bidirectional"))
    )
    (net (code "169") (name "/USR_LVDS12CC_P") (class "Default")
      (node (ref "IC2") (pin "J19") (pinfunction "IO_L12P_T1_MRCC_15_J19") (pintype "bidirectional"))
    )
    (net (code "170") (name "/USR_LVDS13CC_N") (class "Default")
      (node (ref "IC2") (pin "K19") (pinfunction "IO_L13N_T2_MRCC_15_K19") (pintype "bidirectional"))
    )
    (net (code "171") (name "/USR_LVDS13CC_P") (class "Default")
      (node (ref "IC2") (pin "K18") (pinfunction "IO_L13P_T2_MRCC_15_K18") (pintype "bidirectional"))
    )
    (net (code "172") (name "/USR_LVDS14CC_N") (class "Default")
      (node (ref "IC2") (pin "L20") (pinfunction "IO_L14N_T2_SRCC_15_L20") (pintype "bidirectional"))
    )
    (net (code "173") (name "/USR_LVDS14CC_P") (class "Default")
      (node (ref "IC2") (pin "L19") (pinfunction "IO_L14P_T2_SRCC_15_L19") (pintype "bidirectional"))
    )
    (net (code "174") (name "/USR_LVDS15_N") (class "Default")
      (node (ref "IC2") (pin "M22") (pinfunction "IO_L15N_T2_DQS_ADV_B_15_M22") (pintype "bidirectional"))
    )
    (net (code "175") (name "/USR_LVDS15_P") (class "Default")
      (node (ref "IC2") (pin "N22") (pinfunction "IO_L15P_T2_DQS_15_N22") (pintype "bidirectional"))
    )
    (net (code "176") (name "/USR_LVDS16_N") (class "Default")
      (node (ref "IC2") (pin "L18") (pinfunction "IO_L16N_T2_A27_15_L18") (pintype "bidirectional"))
    )
    (net (code "177") (name "/USR_LVDS16_P") (class "Default")
      (node (ref "IC2") (pin "M18") (pinfunction "IO_L16P_T2_A28_15_M18") (pintype "bidirectional"))
    )
    (net (code "178") (name "/USR_LVDS17_N") (class "Default")
      (node (ref "IC2") (pin "N19") (pinfunction "IO_L17N_T2_A25_15_N19") (pintype "bidirectional"))
    )
    (net (code "179") (name "/USR_LVDS17_P") (class "Default")
      (node (ref "IC2") (pin "N18") (pinfunction "IO_L17P_T2_A26_15_N18") (pintype "bidirectional"))
    )
    (net (code "180") (name "/USR_LVDS18_N") (class "Default")
      (node (ref "IC2") (pin "M20") (pinfunction "IO_L18N_T2_A23_15_M20") (pintype "bidirectional"))
    )
    (net (code "181") (name "/USR_LVDS18_P") (class "Default")
      (node (ref "IC2") (pin "N20") (pinfunction "IO_L18P_T2_A24_15_N20") (pintype "bidirectional"))
    )
    (net (code "182") (name "/USR_LVDS19_N") (class "Default")
      (node (ref "IC2") (pin "K14") (pinfunction "IO_L19N_T3_A21_VREF_15_K14") (pintype "bidirectional"))
    )
    (net (code "183") (name "/USR_LVDS19_P") (class "Default")
      (node (ref "IC2") (pin "K13") (pinfunction "IO_L19P_T3_A22_15_K13") (pintype "bidirectional"))
    )
    (net (code "184") (name "/USR_LVDS20_N") (class "Default")
      (node (ref "IC2") (pin "L13") (pinfunction "IO_L20N_T3_A19_15_L13") (pintype "bidirectional"))
    )
    (net (code "185") (name "/USR_LVDS20_P") (class "Default")
      (node (ref "IC2") (pin "M13") (pinfunction "IO_L20P_T3_A20_15_M13") (pintype "bidirectional"))
    )
    (net (code "186") (name "/USR_LVDS21_N") (class "Default")
      (node (ref "IC2") (pin "J17") (pinfunction "IO_L21N_T3_DQS_A18_15_J17") (pintype "bidirectional"))
    )
    (net (code "187") (name "/USR_LVDS21_P") (class "Default")
      (node (ref "IC2") (pin "K17") (pinfunction "IO_L21P_T3_DQS_15_K17") (pintype "bidirectional"))
    )
    (net (code "188") (name "/USR_LVDS22_N") (class "Default")
      (node (ref "IC2") (pin "L15") (pinfunction "IO_L22N_T3_A16_15_L15") (pintype "bidirectional"))
    )
    (net (code "189") (name "/USR_LVDS22_P") (class "Default")
      (node (ref "IC2") (pin "L14") (pinfunction "IO_L22P_T3_A17_15_L14") (pintype "bidirectional"))
    )
    (net (code "190") (name "/USR_LVDS23_N") (class "Default")
      (node (ref "IC2") (pin "K16") (pinfunction "IO_L23N_T3_FWE_B_15_K16") (pintype "bidirectional"))
    )
    (net (code "191") (name "/USR_LVDS23_P") (class "Default")
      (node (ref "IC2") (pin "L16") (pinfunction "IO_L23P_T3_FOE_B_15_L16") (pintype "bidirectional"))
    )
    (net (code "192") (name "/USR_LVDS24_N") (class "Default")
      (node (ref "IC2") (pin "M16") (pinfunction "IO_L24N_T3_RS0_15_M16") (pintype "bidirectional"))
    )
    (net (code "193") (name "/USR_LVDS24_P") (class "Default")
      (node (ref "IC2") (pin "M15") (pinfunction "IO_L24P_T3_RS1_15_M15") (pintype "bidirectional"))
    )
    (net (code "194") (name "GND") (class "Default")
      (node (ref "C48") (pin "2") (pinfunction "2_2") (pintype "passive"))
      (node (ref "C49") (pin "2") (pinfunction "2_2") (pintype "passive"))
      (node (ref "C50") (pin "2") (pinfunction "2_2") (pintype "passive"))
      (node (ref "C51") (pin "2") (pinfunction "2_2") (pintype "passive"))
      (node (ref "C52") (pin "2") (pinfunction "2_2") (pintype "passive"))
      (node (ref "OSC10") (pin "2") (pinfunction "GND_2") (pintype "power_in"))
      (node (ref "R52") (pin "2") (pinfunction "2_2") (pintype "passive"))
    )
    (net (code "195") (name "Net-(IC2A-IO_L16N_T2_A15_D31_14)") (class "Default")
      (node (ref "B19") (pin "1") (pinfunction "1_1") (pintype "bidirectional"))
      (node (ref "IC2") (pin "W17") (pinfunction "IO_L16N_T2_A15_D31_14_W17") (pintype "bidirectional"))
    )
    (net (code "196") (name "Net-(IC2A-IO_L16P_T2_CSI_B_14)") (class "Default")
      (node (ref "B18") (pin "1") (pinfunction "1_1") (pintype "bidirectional"))
      (node (ref "IC2") (pin "V17") (pinfunction "IO_L16P_T2_CSI_B_14_V17") (pintype "bidirectional"))
    )
    (net (code "197") (name "Net-(IC2A-IO_L17N_T2_A13_D29_14)") (class "Default")
      (node (ref "B21") (pin "1") (pinfunction "1_1") (pintype "bidirectional"))
      (node (ref "IC2") (pin "AB18") (pinfunction "IO_L17N_T2_A13_D29_14_AB18") (pintype "bidirectional"))
    )
    (net (code "198") (name "Net-(IC2A-IO_L17P_T2_A14_D30_14)") (class "Default")
      (node (ref "B20") (pin "1") (pinfunction "1_1") (pintype "bidirectional"))
      (node (ref "IC2") (pin "AA18") (pinfunction "IO_L17P_T2_A14_D30_14_AA18") (pintype "bidirectional"))
    )
    (net (code "199") (name "Net-(IC2F-MGTREFCLK0N_216)") (class "Default")
      (node (ref "B15") (pin "1") (pinfunction "1_1") (pintype "bidirectional"))
      (node (ref "IC2") (pin "E6") (pinfunction "MGTREFCLK0N_216_E6") (pintype "input"))
    )
    (net (code "200") (name "Net-(IC2F-MGTREFCLK0P_216)") (class "Default")
      (node (ref "B14") (pin "1") (pinfunction "1_1") (pintype "bidirectional"))
      (node (ref "IC2") (pin "F6") (pinfunction "MGTREFCLK0P_216_F6") (pintype "input"))
    )
    (net (code "201") (name "Net-(IC2F-MGTRREF_216)") (class "Default")
      (node (ref "IC2") (pin "F8") (pinfunction "MGTRREF_216_F8") (pintype "input"))
      (node (ref "R53") (pin "1") (pinfunction "1_1") (pintype "passive"))
    )
    (net (code "202") (name "P1.2VTT") (class "Default")
      (node (ref "R53") (pin "2") (pinfunction "2_2") (pintype "passive"))
    )
    (net (code "203") (name "P3V3") (class "Default")
      (node (ref "C52") (pin "1") (pinfunction "1_1") (pintype "passive"))
      (node (ref "OSC10") (pin "1") (pinfunction "OE_1") (pintype "input"))
      (node (ref "OSC10") (pin "4") (pinfunction "VCC_4") (pintype "power_in"))
    )
    (net (code "204") (name "VTT_REF") (class "Default")
      (node (ref "C48") (pin "1") (pinfunction "1_1") (pintype "passive"))
      (node (ref "C49") (pin "1") (pinfunction "1_1") (pintype "passive"))
      (node (ref "C50") (pin "1") (pinfunction "1_1") (pintype "passive"))
      (node (ref "C51") (pin "1") (pinfunction "1_1") (pintype "passive"))
      (node (ref "IC2") (pin "E3") (pinfunction "IO_L6N_T0_VREF_35_E3") (pintype "bidirectional"))
      (node (ref "IC2") (pin "N3") (pinfunction "IO_L19N_T3_VREF_35_N3") (pintype "bidirectional"))
      (node (ref "IC2") (pin "V3") (pinfunction "IO_L6N_T0_VREF_34_V3") (pintype "bidirectional"))
      (node (ref "IC2") (pin "W7") (pinfunction "IO_L19N_T3_VREF_34_W7") (pintype "bidirectional"))
    )
    (net (code "205") (name "unconnected-(IC2A-IO_0_14-PadP20)") (class "Default")
      (node (ref "IC2") (pin "P20") (pinfunction "IO_0_14_P20") (pintype "bidirectional"))
    )
    (net (code "206") (name "unconnected-(IC2A-IO_25_14-PadN15)") (class "Default")
      (node (ref "IC2") (pin "N15") (pinfunction "IO_25_14_N15") (pintype "bidirectional"))
    )
    (net (code "207") (name "unconnected-(IC2A-IO_L4P_T0_D04_14-PadT21)") (class "Default")
      (node (ref "IC2") (pin "T21") (pinfunction "IO_L4P_T0_D04_14_T21") (pintype "bidirectional"))
    )
    (net (code "208") (name "unconnected-(IC2A-IO_L5N_T0_D07_14-PadR19)") (class "Default")
      (node (ref "IC2") (pin "R19") (pinfunction "IO_L5N_T0_D07_14_R19") (pintype "bidirectional"))
    )
    (net (code "209") (name "unconnected-(IC2A-IO_L5P_T0_D06_14-PadP19)") (class "Default")
      (node (ref "IC2") (pin "P19") (pinfunction "IO_L5P_T0_D06_14_P19") (pintype "bidirectional"))
    )
    (net (code "210") (name "unconnected-(IC2A-IO_L6N_T0_D08_VREF_14-PadT20)") (class "Default")
      (node (ref "IC2") (pin "T20") (pinfunction "IO_L6N_T0_D08_VREF_14_T20") (pintype "bidirectional"))
    )
    (net (code "211") (name "unconnected-(IC2A-IO_L12N_T1_MRCC_14-PadW20)") (class "Default")
      (node (ref "IC2") (pin "W20") (pinfunction "IO_L12N_T1_MRCC_14_W20") (pintype "bidirectional"))
    )
    (net (code "212") (name "unconnected-(IC2A-IO_L14P_T2_SRCC_14-PadV18)") (class "Default")
      (node (ref "IC2") (pin "V18") (pinfunction "IO_L14P_T2_SRCC_14_V18") (pintype "bidirectional"))
    )
    (net (code "213") (name "unconnected-(IC2A-IO_L18N_T2_A11_D27_14-PadU18)") (class "Default")
      (node (ref "IC2") (pin "U18") (pinfunction "IO_L18N_T2_A11_D27_14_U18") (pintype "bidirectional"))
    )
    (net (code "214") (name "unconnected-(IC2A-IO_L19N_T3_A09_D25_VREF_14-PadR14)") (class "Default")
      (node (ref "IC2") (pin "R14") (pinfunction "IO_L19N_T3_A09_D25_VREF_14_R14") (pintype "bidirectional"))
    )
    (net (code "215") (name "unconnected-(IC2A-IO_L19P_T3_A10_D26_14-PadP14)") (class "Default")
      (node (ref "IC2") (pin "P14") (pinfunction "IO_L19P_T3_A10_D26_14_P14") (pintype "bidirectional"))
    )
    (net (code "216") (name "unconnected-(IC2A-IO_L20N_T3_A07_D23_14-PadT18)") (class "Default")
      (node (ref "IC2") (pin "T18") (pinfunction "IO_L20N_T3_A07_D23_14_T18") (pintype "bidirectional"))
    )
    (net (code "217") (name "unconnected-(IC2A-IO_L20P_T3_A08_D24_14-PadR18)") (class "Default")
      (node (ref "IC2") (pin "R18") (pinfunction "IO_L20P_T3_A08_D24_14_R18") (pintype "bidirectional"))
    )
    (net (code "218") (name "unconnected-(IC2A-IO_L21N_T3_DQS_A06_D22_14-PadP17)") (class "Default")
      (node (ref "IC2") (pin "P17") (pinfunction "IO_L21N_T3_DQS_A06_D22_14_P17") (pintype "bidirectional"))
    )
    (net (code "219") (name "unconnected-(IC2A-IO_L21P_T3_DQS_14-PadN17)") (class "Default")
      (node (ref "IC2") (pin "N17") (pinfunction "IO_L21P_T3_DQS_14_N17") (pintype "bidirectional"))
    )
    (net (code "220") (name "unconnected-(IC2A-IO_L22N_T3_A04_D20_14-PadR16)") (class "Default")
      (node (ref "IC2") (pin "R16") (pinfunction "IO_L22N_T3_A04_D20_14_R16") (pintype "bidirectional"))
    )
    (net (code "221") (name "unconnected-(IC2A-IO_L22P_T3_A05_D21_14-PadP15)") (class "Default")
      (node (ref "IC2") (pin "P15") (pinfunction "IO_L22P_T3_A05_D21_14_P15") (pintype "bidirectional"))
    )
    (net (code "222") (name "unconnected-(IC2A-IO_L23N_T3_A02_D18_14-PadN14)") (class "Default")
      (node (ref "IC2") (pin "N14") (pinfunction "IO_L23N_T3_A02_D18_14_N14") (pintype "bidirectional"))
    )
    (net (code "223") (name "unconnected-(IC2A-IO_L23P_T3_A03_D19_14-PadN13)") (class "Default")
      (node (ref "IC2") (pin "N13") (pinfunction "IO_L23P_T3_A03_D19_14_N13") (pintype "bidirectional"))
    )
    (net (code "224") (name "unconnected-(IC2A-IO_L24N_T3_A00_D16_14-PadR17)") (class "Default")
      (node (ref "IC2") (pin "R17") (pinfunction "IO_L24N_T3_A00_D16_14_R17") (pintype "bidirectional"))
    )
    (net (code "225") (name "unconnected-(IC2A-IO_L24P_T3_A01_D17_14-PadP16)") (class "Default")
      (node (ref "IC2") (pin "P16") (pinfunction "IO_L24P_T3_A01_D17_14_P16") (pintype "bidirectional"))
    )
    (net (code "226") (name "unconnected-(IC2B-IO_0_15-PadJ16)") (class "Default")
      (node (ref "IC2") (pin "J16") (pinfunction "IO_0_15_J16") (pintype "bidirectional"))
    )
    (net (code "227") (name "unconnected-(IC2B-IO_25_15-PadM17)") (class "Default")
      (node (ref "IC2") (pin "M17") (pinfunction "IO_25_15_M17") (pintype "bidirectional"))
    )
    (net (code "228") (name "unconnected-(IC2C-IO_0_16-PadF15)") (class "Default")
      (node (ref "IC2") (pin "F15") (pinfunction "IO_0_16_F15") (pintype "bidirectional"))
    )
    (net (code "229") (name "unconnected-(IC2C-IO_25_16-PadF21)") (class "Default")
      (node (ref "IC2") (pin "F21") (pinfunction "IO_25_16_F21") (pintype "bidirectional"))
    )
    (net (code "230") (name "unconnected-(IC2C-IO_L2N_T0_16-PadE17)") (class "Default")
      (node (ref "IC2") (pin "E17") (pinfunction "IO_L2N_T0_16_E17") (pintype "bidirectional"))
    )
    (net (code "231") (name "unconnected-(IC2C-IO_L3N_T0_DQS_16-PadC15)") (class "Default")
      (node (ref "IC2") (pin "C15") (pinfunction "IO_L3N_T0_DQS_16_C15") (pintype "bidirectional"))
    )
    (net (code "232") (name "unconnected-(IC2C-IO_L3P_T0_DQS_16-PadC14)") (class "Default")
      (node (ref "IC2") (pin "C14") (pinfunction "IO_L3P_T0_DQS_16_C14") (pintype "bidirectional"))
    )
    (net (code "233") (name "unconnected-(IC2C-IO_L5N_T0_16-PadD16)") (class "Default")
      (node (ref "IC2") (pin "D16") (pinfunction "IO_L5N_T0_16_D16") (pintype "bidirectional"))
    )
    (net (code "234") (name "unconnected-(IC2C-IO_L6P_T0_16-PadD14)") (class "Default")
      (node (ref "IC2") (pin "D14") (pinfunction "IO_L6P_T0_16_D14") (pintype "bidirectional"))
    )
    (net (code "235") (name "unconnected-(IC2C-IO_L8P_T1_16-PadC13)") (class "Default")
      (node (ref "IC2") (pin "C13") (pinfunction "IO_L8P_T1_16_C13") (pintype "bidirectional"))
    )
    (net (code "236") (name "unconnected-(IC2C-IO_L10N_T1_16-PadA14)") (class "Default")
      (node (ref "IC2") (pin "A14") (pinfunction "IO_L10N_T1_16_A14") (pintype "bidirectional"))
    )
    (net (code "237") (name "unconnected-(IC2C-IO_L11P_T1_SRCC_16-PadB17)") (class "Default")
      (node (ref "IC2") (pin "B17") (pinfunction "IO_L11P_T1_SRCC_16_B17") (pintype "bidirectional"))
    )
    (net (code "238") (name "unconnected-(IC2C-IO_L12N_T1_MRCC_16-PadC17)") (class "Default")
      (node (ref "IC2") (pin "C17") (pinfunction "IO_L12N_T1_MRCC_16_C17") (pintype "bidirectional"))
    )
    (net (code "239") (name "unconnected-(IC2C-IO_L14N_T2_SRCC_16-PadD19)") (class "Default")
      (node (ref "IC2") (pin "D19") (pinfunction "IO_L14N_T2_SRCC_16_D19") (pintype "bidirectional"))
    )
    (net (code "240") (name "unconnected-(IC2C-IO_L14P_T2_SRCC_16-PadE19)") (class "Default")
      (node (ref "IC2") (pin "E19") (pinfunction "IO_L14P_T2_SRCC_16_E19") (pintype "bidirectional"))
    )
    (net (code "241") (name "unconnected-(IC2C-IO_L15N_T2_DQS_16-PadE18)") (class "Default")
      (node (ref "IC2") (pin "E18") (pinfunction "IO_L15N_T2_DQS_16_E18") (pintype "bidirectional"))
    )
    (net (code "242") (name "unconnected-(IC2C-IO_L15P_T2_DQS_16-PadF18)") (class "Default")
      (node (ref "IC2") (pin "F18") (pinfunction "IO_L15P_T2_DQS_16_F18") (pintype "bidirectional"))
    )
    (net (code "243") (name "unconnected-(IC2C-IO_L17P_T2_16-PadA18)") (class "Default")
      (node (ref "IC2") (pin "A18") (pinfunction "IO_L17P_T2_16_A18") (pintype "bidirectional"))
    )
    (net (code "244") (name "unconnected-(IC2C-IO_L18N_T2_16-PadF20)") (class "Default")
      (node (ref "IC2") (pin "F20") (pinfunction "IO_L18N_T2_16_F20") (pintype "bidirectional"))
    )
    (net (code "245") (name "unconnected-(IC2C-IO_L18P_T2_16-PadF19)") (class "Default")
      (node (ref "IC2") (pin "F19") (pinfunction "IO_L18P_T2_16_F19") (pintype "bidirectional"))
    )
    (net (code "246") (name "unconnected-(IC2C-IO_L19P_T3_16-PadD20)") (class "Default")
      (node (ref "IC2") (pin "D20") (pinfunction "IO_L19P_T3_16_D20") (pintype "bidirectional"))
    )
    (net (code "247") (name "unconnected-(IC2C-IO_L20N_T3_16-PadB22)") (class "Default")
      (node (ref "IC2") (pin "B22") (pinfunction "IO_L20N_T3_16_B22") (pintype "bidirectional"))
    )
    (net (code "248") (name "unconnected-(IC2C-IO_L20P_T3_16-PadC22)") (class "Default")
      (node (ref "IC2") (pin "C22") (pinfunction "IO_L20P_T3_16_C22") (pintype "bidirectional"))
    )
    (net (code "249") (name "unconnected-(IC2C-IO_L21N_T3_DQS_16-PadA21)") (class "Default")
      (node (ref "IC2") (pin "A21") (pinfunction "IO_L21N_T3_DQS_16_A21") (pintype "bidirectional"))
    )
    (net (code "250") (name "unconnected-(IC2C-IO_L21P_T3_DQS_16-PadB21)") (class "Default")
      (node (ref "IC2") (pin "B21") (pinfunction "IO_L21P_T3_DQS_16_B21") (pintype "bidirectional"))
    )
    (net (code "251") (name "unconnected-(IC2C-IO_L22N_T3_16-PadD22)") (class "Default")
      (node (ref "IC2") (pin "D22") (pinfunction "IO_L22N_T3_16_D22") (pintype "bidirectional"))
    )
    (net (code "252") (name "unconnected-(IC2C-IO_L22P_T3_16-PadE22)") (class "Default")
      (node (ref "IC2") (pin "E22") (pinfunction "IO_L22P_T3_16_E22") (pintype "bidirectional"))
    )
    (net (code "253") (name "unconnected-(IC2C-IO_L23P_T3_16-PadE21)") (class "Default")
      (node (ref "IC2") (pin "E21") (pinfunction "IO_L23P_T3_16_E21") (pintype "bidirectional"))
    )
    (net (code "254") (name "unconnected-(IC2C-IO_L24N_T3_16-PadG22)") (class "Default")
      (node (ref "IC2") (pin "G22") (pinfunction "IO_L24N_T3_16_G22") (pintype "bidirectional"))
    )
    (net (code "255") (name "unconnected-(IC2C-IO_L24P_T3_16-PadG21)") (class "Default")
      (node (ref "IC2") (pin "G21") (pinfunction "IO_L24P_T3_16_G21") (pintype "bidirectional"))
    )
    (net (code "256") (name "unconnected-(IC2D-IO_0_34-PadT3)") (class "Default")
      (node (ref "IC2") (pin "T3") (pinfunction "IO_0_34_T3") (pintype "bidirectional"))
    )
    (net (code "257") (name "unconnected-(IC2D-IO_25_34-PadU7)") (class "Default")
      (node (ref "IC2") (pin "U7") (pinfunction "IO_25_34_U7") (pintype "bidirectional"))
    )
    (net (code "258") (name "unconnected-(IC2D-IO_L1N_T0_34-PadU1)") (class "Default")
      (node (ref "IC2") (pin "U1") (pinfunction "IO_L1N_T0_34_U1") (pintype "bidirectional"))
    )
    (net (code "259") (name "unconnected-(IC2D-IO_L1P_T0_34-PadT1)") (class "Default")
      (node (ref "IC2") (pin "T1") (pinfunction "IO_L1P_T0_34_T1") (pintype "bidirectional"))
    )
    (net (code "260") (name "unconnected-(IC2D-IO_L2P_T0_34-PadU2)") (class "Default")
      (node (ref "IC2") (pin "U2") (pinfunction "IO_L2P_T0_34_U2") (pintype "bidirectional"))
    )
    (net (code "261") (name "unconnected-(IC2D-IO_L4P_T0_34-PadW2)") (class "Default")
      (node (ref "IC2") (pin "W2") (pinfunction "IO_L4P_T0_34_W2") (pintype "bidirectional"))
    )
    (net (code "262") (name "unconnected-(IC2D-IO_L5P_T0_34-PadW1)") (class "Default")
      (node (ref "IC2") (pin "W1") (pinfunction "IO_L5P_T0_34_W1") (pintype "bidirectional"))
    )
    (net (code "263") (name "unconnected-(IC2D-IO_L6P_T0_34-PadU3)") (class "Default")
      (node (ref "IC2") (pin "U3") (pinfunction "IO_L6P_T0_34_U3") (pintype "bidirectional"))
    )
    (net (code "264") (name "unconnected-(IC2D-IO_L10P_T1_34-PadAA5)") (class "Default")
      (node (ref "IC2") (pin "AA5") (pinfunction "IO_L10P_T1_34_AA5") (pintype "bidirectional"))
    )
    (net (code "265") (name "unconnected-(IC2D-IO_L11N_T1_SRCC_34-PadAA4)") (class "Default")
      (node (ref "IC2") (pin "AA4") (pinfunction "IO_L11N_T1_SRCC_34_AA4") (pintype "bidirectional"))
    )
    (net (code "266") (name "unconnected-(IC2D-IO_L11P_T1_SRCC_34-PadY4)") (class "Default")
      (node (ref "IC2") (pin "Y4") (pinfunction "IO_L11P_T1_SRCC_34_Y4") (pintype "bidirectional"))
    )
    (net (code "267") (name "unconnected-(IC2D-IO_L13N_T2_MRCC_34-PadT4)") (class "Default")
      (node (ref "IC2") (pin "T4") (pinfunction "IO_L13N_T2_MRCC_34_T4") (pintype "bidirectional"))
    )
    (net (code "268") (name "unconnected-(IC2D-IO_L13P_T2_MRCC_34-PadR4)") (class "Default")
      (node (ref "IC2") (pin "R4") (pinfunction "IO_L13P_T2_MRCC_34_R4") (pintype "bidirectional"))
    )
    (net (code "269") (name "unconnected-(IC2D-IO_L14P_T2_SRCC_34-PadT5)") (class "Default")
      (node (ref "IC2") (pin "T5") (pinfunction "IO_L14P_T2_SRCC_34_T5") (pintype "bidirectional"))
    )
    (net (code "270") (name "unconnected-(IC2D-IO_L17N_T2_34-PadT6)") (class "Default")
      (node (ref "IC2") (pin "T6") (pinfunction "IO_L17N_T2_34_T6") (pintype "bidirectional"))
    )
    (net (code "271") (name "unconnected-(IC2D-IO_L17P_T2_34-PadR6)") (class "Default")
      (node (ref "IC2") (pin "R6") (pinfunction "IO_L17P_T2_34_R6") (pintype "bidirectional"))
    )
    (net (code "272") (name "unconnected-(IC2D-IO_L18N_T2_34-PadAA6)") (class "Default")
      (node (ref "IC2") (pin "AA6") (pinfunction "IO_L18N_T2_34_AA6") (pintype "bidirectional"))
    )
    (net (code "273") (name "unconnected-(IC2D-IO_L18P_T2_34-PadY6)") (class "Default")
      (node (ref "IC2") (pin "Y6") (pinfunction "IO_L18P_T2_34_Y6") (pintype "bidirectional"))
    )
    (net (code "274") (name "unconnected-(IC2D-IO_L20N_T3_34-PadAB6)") (class "Default")
      (node (ref "IC2") (pin "AB6") (pinfunction "IO_L20N_T3_34_AB6") (pintype "bidirectional"))
    )
    (net (code "275") (name "unconnected-(IC2D-IO_L20P_T3_34-PadAB7)") (class "Default")
      (node (ref "IC2") (pin "AB7") (pinfunction "IO_L20P_T3_34_AB7") (pintype "bidirectional"))
    )
    (net (code "276") (name "unconnected-(IC2D-IO_L22N_T3_34-PadAB8)") (class "Default")
      (node (ref "IC2") (pin "AB8") (pinfunction "IO_L22N_T3_34_AB8") (pintype "bidirectional"))
    )
    (net (code "277") (name "unconnected-(IC2D-IO_L22P_T3_34-PadAA8)") (class "Default")
      (node (ref "IC2") (pin "AA8") (pinfunction "IO_L22P_T3_34_AA8") (pintype "bidirectional"))
    )
    (net (code "278") (name "unconnected-(IC2E-IO_0_35-PadF4)") (class "Default")
      (node (ref "IC2") (pin "F4") (pinfunction "IO_0_35_F4") (pintype "bidirectional"))
    )
    (net (code "279") (name "unconnected-(IC2E-IO_25_35-PadL6)") (class "Default")
      (node (ref "IC2") (pin "L6") (pinfunction "IO_25_35_L6") (pintype "bidirectional"))
    )
    (net (code "280") (name "unconnected-(IC2E-IO_L12N_T1_MRCC_35-PadG4)") (class "Default")
      (node (ref "IC2") (pin "G4") (pinfunction "IO_L12N_T1_MRCC_35_G4") (pintype "bidirectional"))
    )
    (net (code "281") (name "unconnected-(IC2E-IO_L18N_T2_35-PadL4)") (class "Default")
      (node (ref "IC2") (pin "L4") (pinfunction "IO_L18N_T2_35_L4") (pintype "bidirectional"))
    )
  )
)
